# SolarRS485.net
KiCad netlist of a schematic drawn in EAGLE
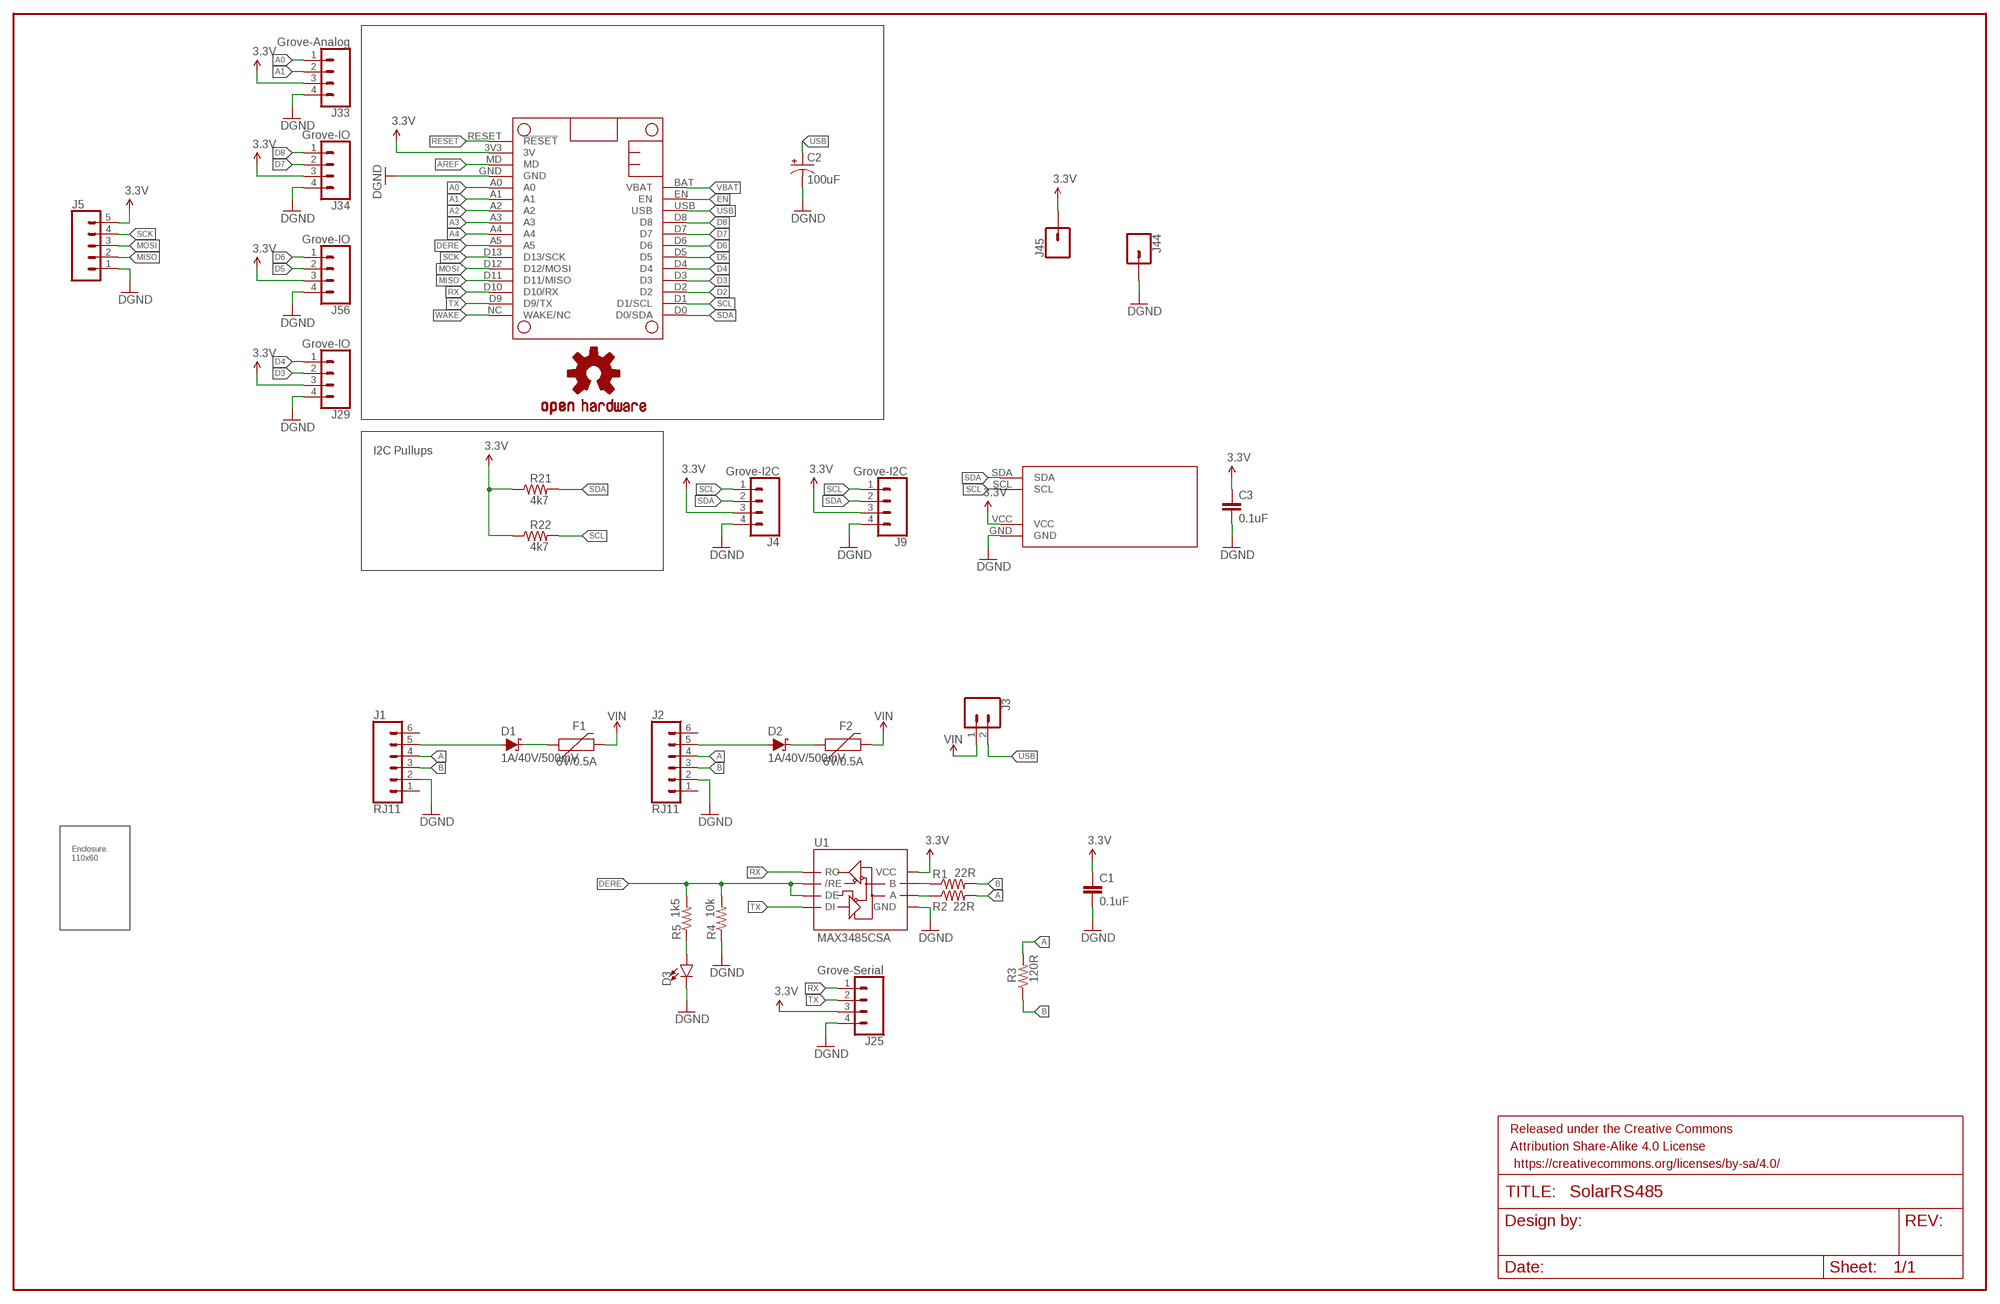
[diagram p0: schematic, sheet 1]

(export (version "E")
  (design (tool "Eeschema 10.0.6"))
  (components
    (comp (ref "C1")
      (value "0.1uF")
      (footprint "eagle-import:0805")
      (libsource (lib "eagle-import") (part "0.1UF-0805-25V"))
    )
    (comp (ref "C2")
      (value "100uF")
      (footprint "eagle-import:CPOL-RADIAL-2.5MM-6.5MM")
      (libsource (lib "eagle-import") (part "100UF-POLAR-RADIAL-2.5MM-25V-20%"))
    )
    (comp (ref "C3")
      (value "0.1uF")
      (footprint "eagle-import:0805")
      (libsource (lib "eagle-import") (part "0.1UF-0805-25V"))
    )
    (comp (ref "D1")
      (value "1A/40V/500mV")
      (footprint "eagle-import:SMA-DIODE")
      (libsource (lib "eagle-import") (part "DIODE-SCHOTTKY-SS14"))
    )
    (comp (ref "D2")
      (value "1A/40V/500mV")
      (footprint "eagle-import:SMA-DIODE")
      (libsource (lib "eagle-import") (part "DIODE-SCHOTTKY-SS14"))
    )
    (comp (ref "D3")
      (value "LEDLED-1206-BOTTOM-2.0MM-BLUE")
      (footprint "eagle-import:LED-1206-BOTTOM-2.0MM")
      (libsource (lib "eagle-import") (part "LEDLED-1206-BOTTOM-2.0MM-BLUE"))
    )
    (comp (ref "F1")
      (value "6V/0.5A")
      (footprint "eagle-import:1206")
      (libsource (lib "eagle-import") (part "PPTC_HALF-AMP"))
    )
    (comp (ref "F2")
      (value "6V/0.5A")
      (footprint "eagle-import:1206")
      (libsource (lib "eagle-import") (part "PPTC_HALF-AMP"))
    )
    (comp (ref "FRAME2")
      (value "FRAME-LEDGER")
      (footprint "eagle-import:CREATIVE_COMMONS")
      (libsource (lib "eagle-import") (part "FRAME-LEDGER"))
    )
    (comp (ref "J1")
      (value "RJ11")
      (footprint "eagle-import:RJ11-6")
      (libsource (lib "eagle-import") (part "RJ11-6"))
    )
    (comp (ref "J2")
      (value "RJ11")
      (footprint "eagle-import:RJ11-6")
      (libsource (lib "eagle-import") (part "RJ11-6"))
    )
    (comp (ref "J3")
      (value "CONN_02")
      (footprint "eagle-import:1X02")
      (libsource (lib "eagle-import") (part "CONN_02"))
    )
    (comp (ref "J4")
      (value "Grove-I2C")
      (footprint "eagle-import:JST-4-PH-GROVE")
      (libsource (lib "eagle-import") (part "CONN_04GROVE-JST-PH-4-2MM"))
    )
    (comp (ref "J5")
      (value "CONN_05")
      (footprint "eagle-import:1X05")
      (libsource (lib "eagle-import") (part "CONN_05"))
    )
    (comp (ref "J9")
      (value "Grove-I2C")
      (footprint "eagle-import:JST-4-PH-GROVE")
      (libsource (lib "eagle-import") (part "CONN_04GROVE-JST-PH-4-2MM"))
    )
    (comp (ref "J25")
      (value "Grove-Serial")
      (footprint "eagle-import:JST-4-PH-GROVE")
      (libsource (lib "eagle-import") (part "CONN_04GROVE-JST-PH-4-2MM"))
    )
    (comp (ref "J29")
      (value "Grove-IO")
      (footprint "eagle-import:JST-4-PH-GROVE")
      (libsource (lib "eagle-import") (part "CONN_04GROVE-JST-PH-4-2MM"))
    )
    (comp (ref "J33")
      (value "Grove-Analog")
      (footprint "eagle-import:JST-4-PH-GROVE")
      (libsource (lib "eagle-import") (part "CONN_04GROVE-JST-PH-4-2MM"))
    )
    (comp (ref "J34")
      (value "Grove-IO")
      (footprint "eagle-import:JST-4-PH-GROVE")
      (libsource (lib "eagle-import") (part "CONN_04GROVE-JST-PH-4-2MM"))
    )
    (comp (ref "J44")
      (value "CONN_01PTH_NO_SILK_YES_STOP")
      (footprint "eagle-import:1X01_NO_SILK")
      (libsource (lib "eagle-import") (part "CONN_01PTH_NO_SILK_YES_STOP"))
    )
    (comp (ref "J45")
      (value "CONN_01PTH_NO_SILK_YES_STOP")
      (footprint "eagle-import:1X01_NO_SILK")
      (libsource (lib "eagle-import") (part "CONN_01PTH_NO_SILK_YES_STOP"))
    )
    (comp (ref "J56")
      (value "Grove-IO")
      (footprint "eagle-import:JST-4-PH-GROVE")
      (libsource (lib "eagle-import") (part "CONN_04GROVE-JST-PH-4-2MM"))
    )
    (comp (ref "LOGO1")
      (value "OSHW-LOGOM")
      (footprint "eagle-import:OSHW-LOGO-M")
      (libsource (lib "eagle-import") (part "OSHW-LOGOM"))
    )
    (comp (ref "MS1")
      (value "XENONA")
      (footprint "eagle-import:XENON_BREAKOUT_A")
      (libsource (lib "eagle-import") (part "XENONA"))
    )
    (comp (ref "R1")
      (value "22R")
      (footprint "eagle-import:0805")
      (libsource (lib "eagle-import") (part "RESISTOR0805"))
    )
    (comp (ref "R2")
      (value "22R")
      (footprint "eagle-import:0805")
      (libsource (lib "eagle-import") (part "RESISTOR0805"))
    )
    (comp (ref "R3")
      (value "120R")
      (footprint "eagle-import:0805")
      (libsource (lib "eagle-import") (part "RESISTOR0805"))
    )
    (comp (ref "R4")
      (value "10k")
      (footprint "eagle-import:0805")
      (libsource (lib "eagle-import") (part "RESISTOR0805"))
    )
    (comp (ref "R5")
      (value "1k5")
      (footprint "eagle-import:0805")
      (libsource (lib "eagle-import") (part "RESISTOR0805"))
    )
    (comp (ref "R21")
      (value "4k7")
      (footprint "eagle-import:0805")
      (libsource (lib "eagle-import") (part "RESISTOR0805"))
    )
    (comp (ref "R22")
      (value "4k7")
      (footprint "eagle-import:0805")
      (libsource (lib "eagle-import") (part "RESISTOR0805"))
    )
    (comp (ref "U$1")
      (value "CAMDENBOSS-ENCLOSURE-110X60BOTH-EXTENDED-WIDE")
      (footprint "eagle-import:CAMDENBOSS_ENCLOSURE_110X60_WIDE_EXTENDED")
      (libsource (lib "eagle-import") (part "CAMDENBOSS-ENCLOSURE-110X60BOTH-EXTENDED-WIDE"))
    )
    (comp (ref "U$2")
      (value "DISPLAY0.96_INCH_DISPLAY")
      (footprint "eagle-import:I2C_DISPLAY_0.96_INCH")
      (libsource (lib "eagle-import") (part "DISPLAY0.96_INCH_DISPLAY"))
    )
    (comp (ref "U1")
      (value "MAX3485CSA")
      (footprint "eagle-import:SO08")
      (libsource (lib "eagle-import") (part "RS485SOIC"))
    )
  )
  (nets
    (net (code "1") (name "3.3V") (class "Default")
      (node (ref "C1") (pin "1") (pinfunction "1_1") (pintype "passive"))
      (node (ref "C3") (pin "1") (pinfunction "1_1") (pintype "passive"))
      (node (ref "J25") (pin "3") (pinfunction "3_3") (pintype "passive"))
      (node (ref "J29") (pin "3") (pinfunction "3_3") (pintype "passive"))
      (node (ref "J33") (pin "3") (pinfunction "3_3") (pintype "passive"))
      (node (ref "J34") (pin "3") (pinfunction "3_3") (pintype "passive"))
      (node (ref "J4") (pin "3") (pinfunction "3_3") (pintype "passive"))
      (node (ref "J45") (pin "1") (pinfunction "1_1") (pintype "passive"))
      (node (ref "J5") (pin "5") (pinfunction "5_5") (pintype "passive"))
      (node (ref "J56") (pin "3") (pinfunction "3_3") (pintype "passive"))
      (node (ref "J9") (pin "3") (pinfunction "3_3") (pintype "passive"))
      (node (ref "MS1") (pin "3V3") (pinfunction "3V_3V3") (pintype "power_in"))
      (node (ref "R21") (pin "1") (pinfunction "1_1") (pintype "passive"))
      (node (ref "R22") (pin "1") (pinfunction "1_1") (pintype "passive"))
      (node (ref "U$2") (pin "VCC") (pinfunction "VCC_VCC") (pintype "power_in"))
      (node (ref "U1") (pin "8") (pinfunction "VCC_8") (pintype "bidirectional"))
    )
    (net (code "2") (name "A") (class "Default")
      (node (ref "J1") (pin "4") (pinfunction "4_4") (pintype "passive"))
      (node (ref "J2") (pin "4") (pinfunction "4_4") (pintype "passive"))
      (node (ref "R2") (pin "2") (pinfunction "2_2") (pintype "passive"))
      (node (ref "R3") (pin "2") (pinfunction "2_2") (pintype "passive"))
    )
    (net (code "3") (name "A0") (class "Default")
      (node (ref "J33") (pin "1") (pinfunction "1_1") (pintype "passive"))
      (node (ref "MS1") (pin "A0") (pinfunction "A0_A0") (pintype "bidirectional"))
    )
    (net (code "4") (name "A1") (class "Default")
      (node (ref "J33") (pin "2") (pinfunction "2_2") (pintype "passive"))
      (node (ref "MS1") (pin "A1") (pinfunction "A1_A1") (pintype "bidirectional"))
    )
    (net (code "5") (name "A2") (class "Default")
      (node (ref "MS1") (pin "A2") (pinfunction "A2_A2") (pintype "bidirectional"))
    )
    (net (code "6") (name "A3") (class "Default")
      (node (ref "MS1") (pin "A3") (pinfunction "A3_A3") (pintype "bidirectional"))
    )
    (net (code "7") (name "A4") (class "Default")
      (node (ref "MS1") (pin "A4") (pinfunction "A4_A4") (pintype "bidirectional"))
    )
    (net (code "8") (name "AREF") (class "Default")
      (node (ref "MS1") (pin "MD") (pinfunction "MD_MD") (pintype "passive"))
    )
    (net (code "9") (name "B") (class "Default")
      (node (ref "J1") (pin "3") (pinfunction "3_3") (pintype "passive"))
      (node (ref "J2") (pin "3") (pinfunction "3_3") (pintype "passive"))
      (node (ref "R1") (pin "2") (pinfunction "2_2") (pintype "passive"))
      (node (ref "R3") (pin "1") (pinfunction "1_1") (pintype "passive"))
    )
    (net (code "10") (name "D2") (class "Default")
      (node (ref "MS1") (pin "D2") (pinfunction "D2_D2") (pintype "bidirectional"))
    )
    (net (code "11") (name "D3") (class "Default")
      (node (ref "J29") (pin "2") (pinfunction "2_2") (pintype "passive"))
      (node (ref "MS1") (pin "D3") (pinfunction "D3_D3") (pintype "bidirectional"))
    )
    (net (code "12") (name "D4") (class "Default")
      (node (ref "J29") (pin "1") (pinfunction "1_1") (pintype "passive"))
      (node (ref "MS1") (pin "D4") (pinfunction "D4_D4") (pintype "bidirectional"))
    )
    (net (code "13") (name "D5") (class "Default")
      (node (ref "J56") (pin "2") (pinfunction "2_2") (pintype "passive"))
      (node (ref "MS1") (pin "D5") (pinfunction "D5_D5") (pintype "bidirectional"))
    )
    (net (code "14") (name "D6") (class "Default")
      (node (ref "J56") (pin "1") (pinfunction "1_1") (pintype "passive"))
      (node (ref "MS1") (pin "D6") (pinfunction "D6_D6") (pintype "bidirectional"))
    )
    (net (code "15") (name "D7") (class "Default")
      (node (ref "J34") (pin "2") (pinfunction "2_2") (pintype "passive"))
      (node (ref "MS1") (pin "D7") (pinfunction "D7_D7") (pintype "bidirectional"))
    )
    (net (code "16") (name "D8") (class "Default")
      (node (ref "J34") (pin "1") (pinfunction "1_1") (pintype "passive"))
      (node (ref "MS1") (pin "D8") (pinfunction "D8_D8") (pintype "bidirectional"))
    )
    (net (code "17") (name "DERE") (class "Default")
      (node (ref "MS1") (pin "A5") (pinfunction "A5_A5") (pintype "bidirectional"))
      (node (ref "R4") (pin "2") (pinfunction "2_2") (pintype "passive"))
      (node (ref "R5") (pin "2") (pinfunction "2_2") (pintype "passive"))
      (node (ref "U1") (pin "2") (pinfunction "/RE_2") (pintype "bidirectional"))
      (node (ref "U1") (pin "3") (pinfunction "DE_3") (pintype "bidirectional"))
    )
    (net (code "18") (name "DGND") (class "Default")
      (node (ref "C1") (pin "2") (pinfunction "2_2") (pintype "passive"))
      (node (ref "C2") (pin "2") (pinfunction "-_2") (pintype "passive"))
      (node (ref "C3") (pin "2") (pinfunction "2_2") (pintype "passive"))
      (node (ref "D3") (pin "C") (pinfunction "C_C") (pintype "passive"))
      (node (ref "J1") (pin "2") (pinfunction "2_2") (pintype "passive"))
      (node (ref "J2") (pin "2") (pinfunction "2_2") (pintype "passive"))
      (node (ref "J25") (pin "4") (pinfunction "4_4") (pintype "passive"))
      (node (ref "J29") (pin "4") (pinfunction "4_4") (pintype "passive"))
      (node (ref "J33") (pin "4") (pinfunction "4_4") (pintype "passive"))
      (node (ref "J34") (pin "4") (pinfunction "4_4") (pintype "passive"))
      (node (ref "J4") (pin "4") (pinfunction "4_4") (pintype "passive"))
      (node (ref "J44") (pin "1") (pinfunction "1_1") (pintype "passive"))
      (node (ref "J5") (pin "1") (pinfunction "1_1") (pintype "passive"))
      (node (ref "J56") (pin "4") (pinfunction "4_4") (pintype "passive"))
      (node (ref "J9") (pin "4") (pinfunction "4_4") (pintype "passive"))
      (node (ref "MS1") (pin "GND") (pinfunction "GND_GND") (pintype "power_in"))
      (node (ref "R4") (pin "1") (pinfunction "1_1") (pintype "passive"))
      (node (ref "U$2") (pin "GND") (pinfunction "GND_GND") (pintype "power_in"))
      (node (ref "U1") (pin "5") (pinfunction "GND_5") (pintype "bidirectional"))
    )
    (net (code "19") (name "EN") (class "Default")
      (node (ref "MS1") (pin "EN") (pinfunction "EN_EN") (pintype "passive"))
    )
    (net (code "20") (name "MISO") (class "Default")
      (node (ref "J5") (pin "2") (pinfunction "2_2") (pintype "passive"))
      (node (ref "MS1") (pin "D11") (pinfunction "D11/MISO_D11") (pintype "bidirectional"))
    )
    (net (code "21") (name "MOSI") (class "Default")
      (node (ref "J5") (pin "3") (pinfunction "3_3") (pintype "passive"))
      (node (ref "MS1") (pin "D12") (pinfunction "D12/MOSI_D12") (pintype "bidirectional"))
    )
    (net (code "22") (name "Net-(D1-PadA)") (class "Default")
      (node (ref "D1") (pin "A") (pinfunction "A_A") (pintype "passive"))
      (node (ref "J1") (pin "5") (pinfunction "5_5") (pintype "passive"))
    )
    (net (code "23") (name "Net-(D1-PadC)") (class "Default")
      (node (ref "D1") (pin "C") (pinfunction "C_C") (pintype "passive"))
      (node (ref "F1") (pin "1") (pinfunction "1_1") (pintype "bidirectional"))
    )
    (net (code "24") (name "Net-(D2-PadA)") (class "Default")
      (node (ref "D2") (pin "A") (pinfunction "A_A") (pintype "passive"))
      (node (ref "J2") (pin "5") (pinfunction "5_5") (pintype "passive"))
    )
    (net (code "25") (name "Net-(D2-PadC)") (class "Default")
      (node (ref "D2") (pin "C") (pinfunction "C_C") (pintype "passive"))
      (node (ref "F2") (pin "1") (pinfunction "1_1") (pintype "bidirectional"))
    )
    (net (code "26") (name "Net-(D3-PadA)") (class "Default")
      (node (ref "D3") (pin "A") (pinfunction "A_A") (pintype "passive"))
      (node (ref "R5") (pin "1") (pinfunction "1_1") (pintype "passive"))
    )
    (net (code "27") (name "Net-(U1-A)") (class "Default")
      (node (ref "R2") (pin "1") (pinfunction "1_1") (pintype "passive"))
      (node (ref "U1") (pin "6") (pinfunction "A_6") (pintype "bidirectional"))
    )
    (net (code "28") (name "Net-(U1-B)") (class "Default")
      (node (ref "R1") (pin "1") (pinfunction "1_1") (pintype "passive"))
      (node (ref "U1") (pin "7") (pinfunction "B_7") (pintype "bidirectional"))
    )
    (net (code "29") (name "RESET") (class "Default")
      (node (ref "MS1") (pin "RESET") (pinfunction "~{RESET}_RESET") (pintype "input"))
    )
    (net (code "30") (name "RX") (class "Default")
      (node (ref "J25") (pin "1") (pinfunction "1_1") (pintype "passive"))
      (node (ref "MS1") (pin "D10") (pinfunction "D10/RX_D10") (pintype "bidirectional"))
      (node (ref "U1") (pin "1") (pinfunction "RO_1") (pintype "bidirectional"))
    )
    (net (code "31") (name "SCK") (class "Default")
      (node (ref "J5") (pin "4") (pinfunction "4_4") (pintype "passive"))
      (node (ref "MS1") (pin "D13") (pinfunction "D13/SCK_D13") (pintype "bidirectional"))
    )
    (net (code "32") (name "SCL") (class "Default")
      (node (ref "J4") (pin "1") (pinfunction "1_1") (pintype "passive"))
      (node (ref "J9") (pin "1") (pinfunction "1_1") (pintype "passive"))
      (node (ref "MS1") (pin "D1") (pinfunction "D1/SCL_D1") (pintype "bidirectional"))
      (node (ref "R22") (pin "2") (pinfunction "2_2") (pintype "passive"))
      (node (ref "U$2") (pin "SCL") (pinfunction "SCL_SCL") (pintype "bidirectional"))
    )
    (net (code "33") (name "SDA") (class "Default")
      (node (ref "J4") (pin "2") (pinfunction "2_2") (pintype "passive"))
      (node (ref "J9") (pin "2") (pinfunction "2_2") (pintype "passive"))
      (node (ref "MS1") (pin "D0") (pinfunction "D0/SDA_D0") (pintype "bidirectional"))
      (node (ref "R21") (pin "2") (pinfunction "2_2") (pintype "passive"))
      (node (ref "U$2") (pin "SDA") (pinfunction "SDA_SDA") (pintype "bidirectional"))
    )
    (net (code "34") (name "TX") (class "Default")
      (node (ref "J25") (pin "2") (pinfunction "2_2") (pintype "passive"))
      (node (ref "MS1") (pin "D9") (pinfunction "D9/TX_D9") (pintype "bidirectional"))
      (node (ref "U1") (pin "4") (pinfunction "DI_4") (pintype "bidirectional"))
    )
    (net (code "35") (name "USB") (class "Default")
      (node (ref "C2") (pin "1") (pinfunction "+_1") (pintype "passive"))
      (node (ref "J3") (pin "2") (pinfunction "2_2") (pintype "passive"))
      (node (ref "MS1") (pin "USB") (pinfunction "USB_USB") (pintype "power_in"))
    )
    (net (code "36") (name "VBAT") (class "Default")
      (node (ref "MS1") (pin "BAT") (pinfunction "VBAT_BAT") (pintype "power_in"))
    )
    (net (code "37") (name "VIN") (class "Default")
      (node (ref "F1") (pin "2") (pinfunction "2_2") (pintype "bidirectional"))
      (node (ref "F2") (pin "2") (pinfunction "2_2") (pintype "bidirectional"))
      (node (ref "J3") (pin "1") (pinfunction "1_1") (pintype "passive"))
    )
    (net (code "38") (name "WAKE") (class "Default")
      (node (ref "MS1") (pin "NC") (pinfunction "WAKE/NC_NC") (pintype "passive"))
    )
    (net (code "39") (name "unconnected-(J1-Pad1)") (class "Default")
      (node (ref "J1") (pin "1") (pinfunction "1_1") (pintype "passive"))
    )
    (net (code "40") (name "unconnected-(J1-Pad6)") (class "Default")
      (node (ref "J1") (pin "6") (pinfunction "6_6") (pintype "passive"))
    )
    (net (code "41") (name "unconnected-(J2-Pad1)") (class "Default")
      (node (ref "J2") (pin "1") (pinfunction "1_1") (pintype "passive"))
    )
    (net (code "42") (name "unconnected-(J2-Pad6)") (class "Default")
      (node (ref "J2") (pin "6") (pinfunction "6_6") (pintype "passive"))
    )
  )
)
